# rv_ledbrick_top.net
KiCad netlist of a schematic drawn in Altium Designer
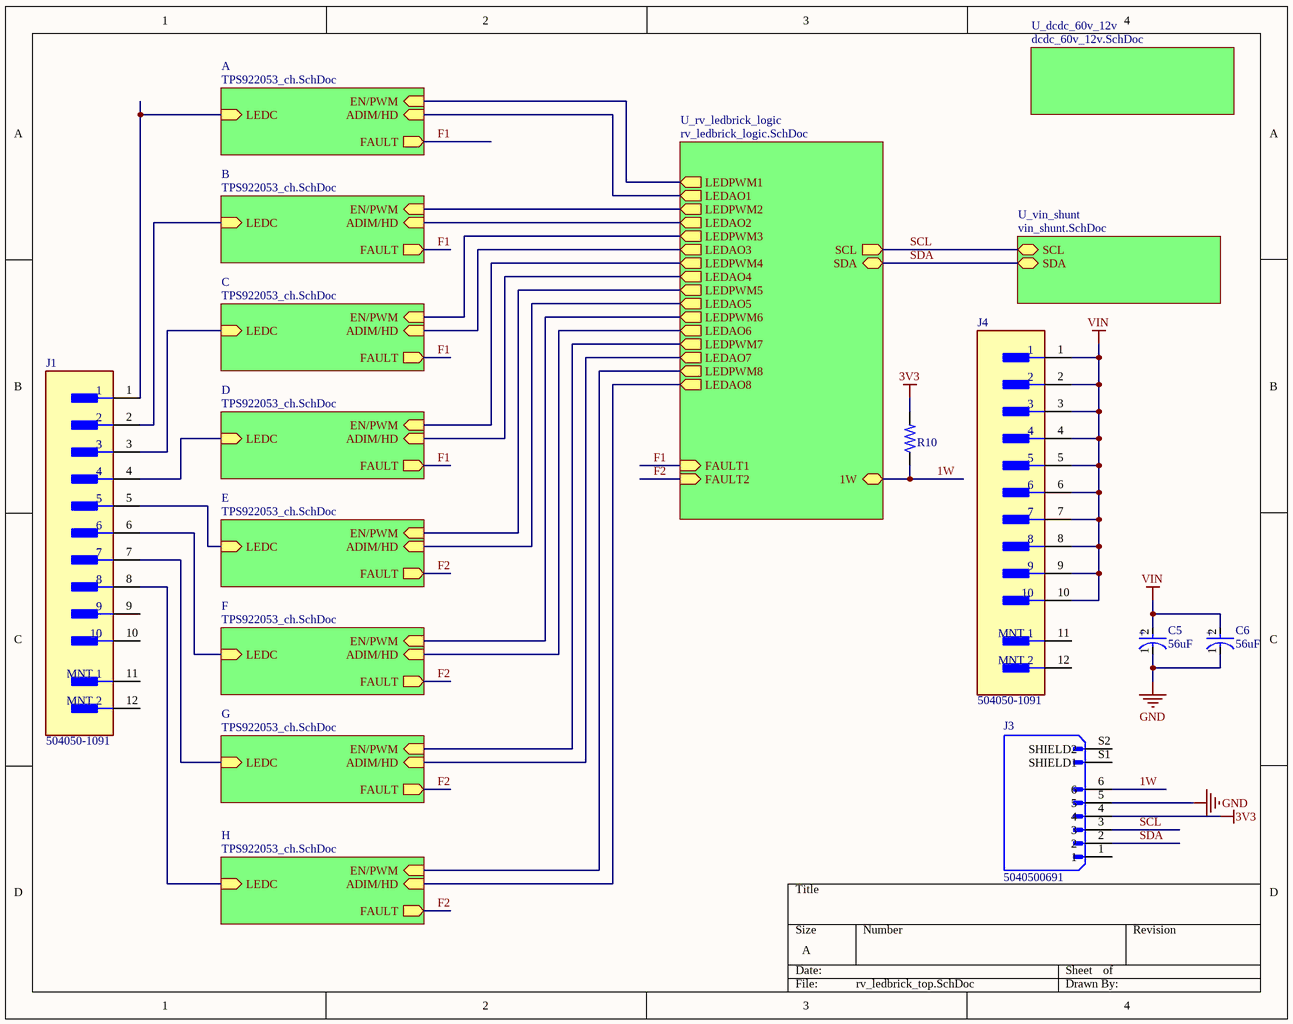
[diagram p0: rv_ledbrick_top.SchDoc]

(export (version "E")
  (design (tool "Eeschema 10.0.6"))
  (components
    (comp (ref "C5")
      (value "56uF")
      (footprint "FP-OS-CON-SMT-F12-MFG")
      (description "Conductive Polymer Aluminum Solid Capacitor 56uF 20% 80V Surface Mount T/R")
      (fields (field (name "TOLERANCE") "20%") (field (name "Comment") "CAP 56uF 80V Poly"))
      (libsource (lib "StackFoundry LLC") (part "a7907c86e72a156c28511143de7831b"))
    )
    (comp (ref "C6")
      (value "56uF")
      (footprint "FP-OS-CON-SMT-F12-MFG")
      (description "Conductive Polymer Aluminum Solid Capacitor 56uF 20% 80V Surface Mount T/R")
      (fields (field (name "TOLERANCE") "20%") (field (name "Comment") "CAP 56uF 80V Poly"))
      (libsource (lib "StackFoundry LLC") (part "a7907c86e72a156c28511143de7831b"))
    )
    (comp (ref "J1")
      (value "504050-1091")
      (footprint "FP-504050-1091-MFG")
      (description "Conn Wire to Board HDR 10 POS 1.5mm Solder RA SMD Pico-Lock™ T/R")
      (libsource (lib "StackFoundry LLC") (part "6fa52caac0d1ee56d9e6a1d806c5b84"))
    )
    (comp (ref "J3")
      (value "5040500691")
      (footprint "MOLEX_5040500691")
      (description "CONN WIRE TO BOARD RA 6POS")
      (libsource (lib "StackFoundry LLC") (part "5040500691"))
    )
    (comp (ref "J4")
      (value "504050-1091")
      (footprint "FP-504050-1091-MFG")
      (description "Conn Wire to Board HDR 10 POS 1.5mm Solder RA SMD Pico-Lock™ T/R")
      (libsource (lib "StackFoundry LLC") (part "6fa52caac0d1ee56d9e6a1d806c5b84"))
    )
    (comp (ref "R10")
      (value "4.7k 0603 1%")
      (footprint "RESC1608-IPC-LL")
      (description "RES SMD 4.7K OHM 1% 1/10W 0603")
      (libsource (lib "StackFoundry LLC") (part "R-US"))
    )
  )
  (nets
    (net (code "1") (name "/1W") (class "Default")
      (node (ref "J3") (pin "6") (pinfunction "6_6") (pintype "passive"))
      (node (ref "R10") (pin "1") (pinfunction "1_1") (pintype "passive"))
    )
    (net (code "12") (name "/LEDC") (class "Default")
      (node (ref "J1") (pin "4") (pinfunction "4_4") (pintype "passive"))
    )
    (net (code "13") (name "/LEDC_1") (class "Default")
      (node (ref "J1") (pin "1") (pinfunction "1_1") (pintype "passive"))
    )
    (net (code "14") (name "/LEDC_2") (class "Default")
      (node (ref "J1") (pin "2") (pinfunction "2_2") (pintype "passive"))
    )
    (net (code "15") (name "/LEDC_3") (class "Default")
      (node (ref "J1") (pin "3") (pinfunction "3_3") (pintype "passive"))
    )
    (net (code "16") (name "/LEDC_4") (class "Default")
      (node (ref "J1") (pin "5") (pinfunction "5_5") (pintype "passive"))
    )
    (net (code "17") (name "/LEDC_5") (class "Default")
      (node (ref "J1") (pin "6") (pinfunction "6_6") (pintype "passive"))
    )
    (net (code "18") (name "/LEDC_6") (class "Default")
      (node (ref "J1") (pin "7") (pinfunction "7_7") (pintype "passive"))
    )
    (net (code "19") (name "/LEDC_7") (class "Default")
      (node (ref "J1") (pin "8") (pinfunction "8_8") (pintype "passive"))
    )
    (net (code "28") (name "/SCL") (class "Default")
      (node (ref "J3") (pin "3") (pinfunction "3_3") (pintype "passive"))
    )
    (net (code "29") (name "/SDA") (class "Default")
      (node (ref "J3") (pin "2") (pinfunction "2_2") (pintype "passive"))
    )
    (net (code "30") (name "3V3") (class "Default")
      (node (ref "J3") (pin "4") (pinfunction "4_4") (pintype "passive"))
      (node (ref "R10") (pin "2") (pinfunction "2_2") (pintype "passive"))
    )
    (net (code "31") (name "GND") (class "Default")
      (node (ref "C5") (pin "1") (pinfunction "C_1") (pintype "passive"))
      (node (ref "C6") (pin "1") (pinfunction "C_1") (pintype "passive"))
      (node (ref "J3") (pin "5") (pinfunction "5_5") (pintype "passive"))
    )
    (net (code "32") (name "VIN") (class "Default")
      (node (ref "C5") (pin "2") (pinfunction "A_2") (pintype "passive"))
      (node (ref "C6") (pin "2") (pinfunction "A_2") (pintype "passive"))
      (node (ref "J4") (pin "1") (pinfunction "1_1") (pintype "passive"))
      (node (ref "J4") (pin "10") (pinfunction "10_10") (pintype "passive"))
      (node (ref "J4") (pin "2") (pinfunction "2_2") (pintype "passive"))
      (node (ref "J4") (pin "3") (pinfunction "3_3") (pintype "passive"))
      (node (ref "J4") (pin "4") (pinfunction "4_4") (pintype "passive"))
      (node (ref "J4") (pin "5") (pinfunction "5_5") (pintype "passive"))
      (node (ref "J4") (pin "6") (pinfunction "6_6") (pintype "passive"))
      (node (ref "J4") (pin "7") (pinfunction "7_7") (pintype "passive"))
      (node (ref "J4") (pin "8") (pinfunction "8_8") (pintype "passive"))
      (node (ref "J4") (pin "9") (pinfunction "9_9") (pintype "passive"))
    )
    (net (code "33") (name "unconnected-(J1-MNT_1-Pad11)") (class "Default")
      (node (ref "J1") (pin "11") (pinfunction "MNT_1_11") (pintype "passive"))
    )
    (net (code "34") (name "unconnected-(J1-MNT_2-Pad12)") (class "Default")
      (node (ref "J1") (pin "12") (pinfunction "MNT_2_12") (pintype "passive"))
    )
    (net (code "35") (name "unconnected-(J1-Pad9)") (class "Default")
      (node (ref "J1") (pin "9") (pinfunction "9_9") (pintype "passive"))
    )
    (net (code "36") (name "unconnected-(J1-Pad10)") (class "Default")
      (node (ref "J1") (pin "10") (pinfunction "10_10") (pintype "passive"))
    )
    (net (code "37") (name "unconnected-(J3-Pad1)") (class "Default")
      (node (ref "J3") (pin "1") (pinfunction "1_1") (pintype "passive"))
    )
    (net (code "38") (name "unconnected-(J3-SHIELD1-PadS1)") (class "Default")
      (node (ref "J3") (pin "S1") (pinfunction "SHIELD1_S1") (pintype "passive"))
    )
    (net (code "39") (name "unconnected-(J3-SHIELD2-PadS2)") (class "Default")
      (node (ref "J3") (pin "S2") (pinfunction "SHIELD2_S2") (pintype "passive"))
    )
    (net (code "40") (name "unconnected-(J4-MNT_1-Pad11)") (class "Default")
      (node (ref "J4") (pin "11") (pinfunction "MNT_1_11") (pintype "passive"))
    )
    (net (code "41") (name "unconnected-(J4-MNT_2-Pad12)") (class "Default")
      (node (ref "J4") (pin "12") (pinfunction "MNT_2_12") (pintype "passive"))
    )
  )
)
